# 1_HV_POWER.net
KiCad netlist of a schematic drawn in Altium Designer
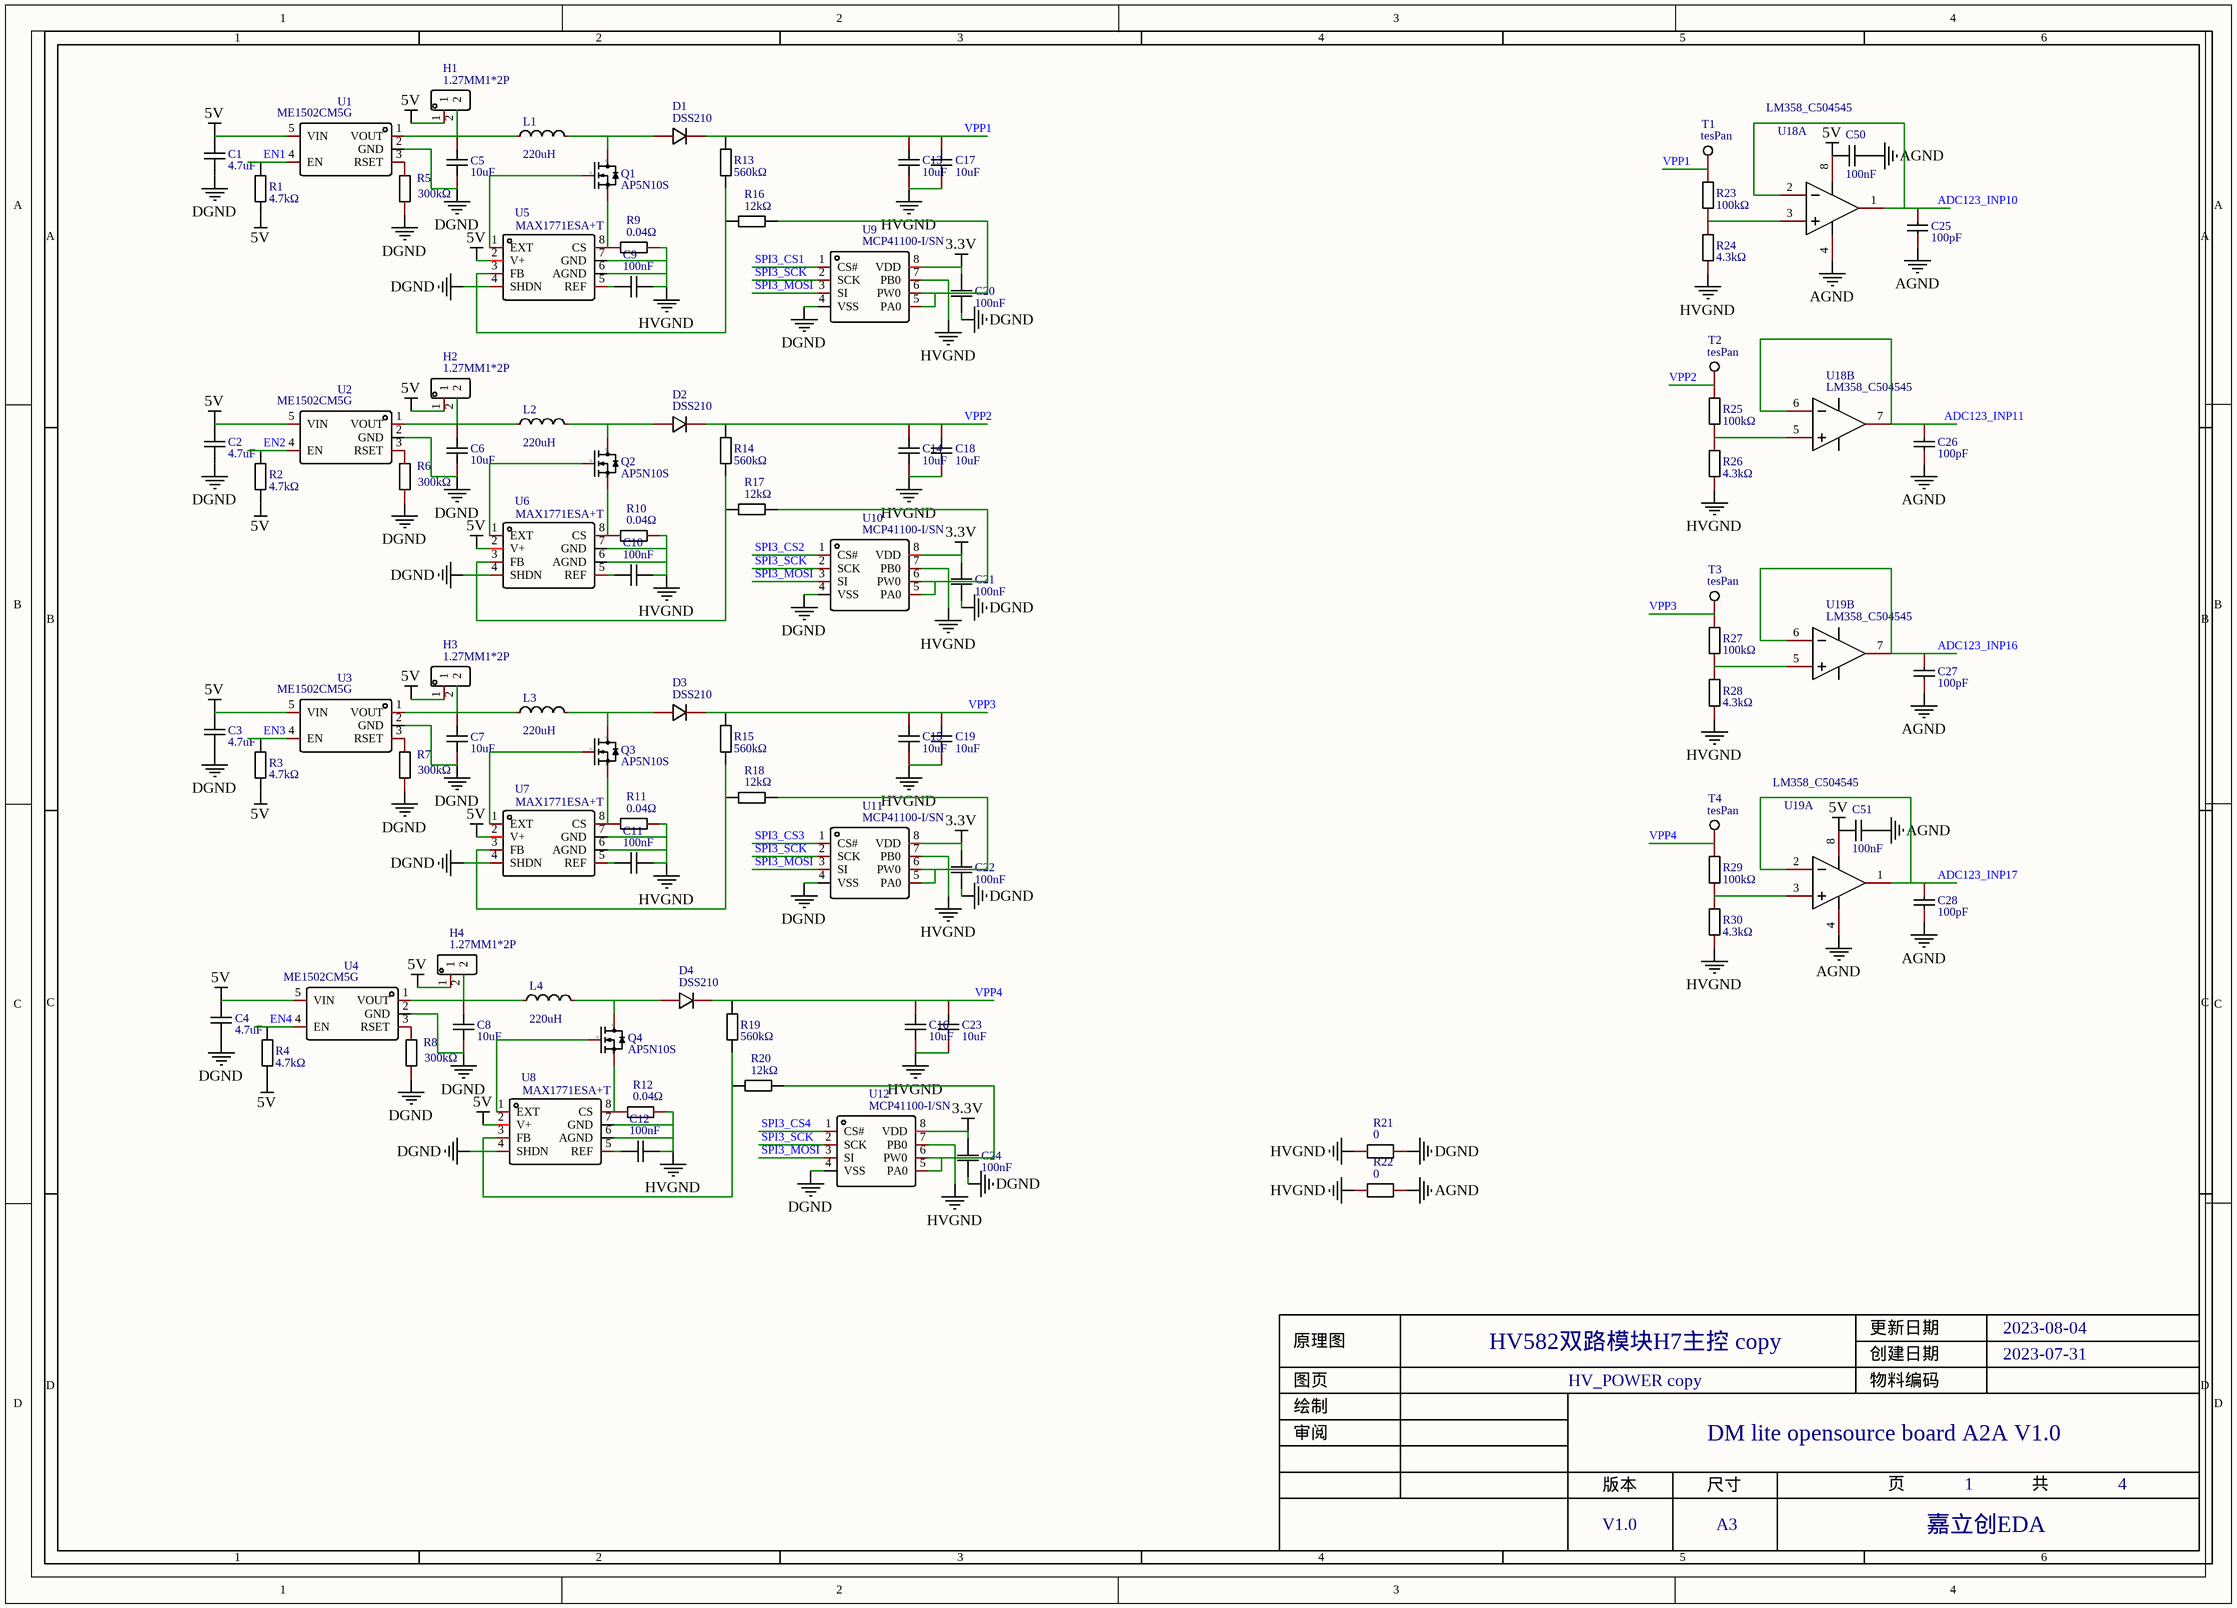
[diagram p0: 1_HV_POWER.schdoc]

(export (version "E")
  (design (tool "Eeschema 10.0.6"))
  (components
    (comp (ref "C1")
      (value "4.7uF")
      (fields
        (field (name "NAME") "4.7uF")
        (field (name "MANUFACTURER PART") "CL05A475MP5NRNC")
        (field (name "MANUFACTURER") "SAMSUNG(三星)")
      )
      (libsource (lib "altium-import") (part "root_1_4.7uF_"))
    )
    (comp (ref "C2")
      (value "4.7uF")
      (fields
        (field (name "NAME") "4.7uF")
        (field (name "MANUFACTURER PART") "CL05A475MP5NRNC")
        (field (name "MANUFACTURER") "SAMSUNG(三星)")
      )
      (libsource (lib "altium-import") (part "root_1_4.7uF_C0402_"))
    )
    (comp (ref "C3")
      (value "4.7uF")
      (fields
        (field (name "NAME") "4.7uF")
        (field (name "MANUFACTURER PART") "CL05A475MP5NRNC")
        (field (name "MANUFACTURER") "SAMSUNG(三星)")
      )
      (libsource (lib "altium-import") (part "root_1_4.7uF_C0402_"))
    )
    (comp (ref "C4")
      (value "4.7uF")
      (fields
        (field (name "NAME") "4.7uF")
        (field (name "MANUFACTURER PART") "CL05A475MP5NRNC")
        (field (name "MANUFACTURER") "SAMSUNG(三星)")
      )
      (libsource (lib "altium-import") (part "root_1_4.7uF_C0402_"))
    )
    (comp (ref "C5")
      (value "10uF")
      (fields
        (field (name "NAME") "10uF")
        (field (name "MANUFACTURER") "Samsung Electro-Mechanics")
        (field (name "MANUFACTURER PART") "CL05A106MP5NUNC")
      )
      (libsource (lib "altium-import") (part "root_1_10uF_C0402_"))
    )
    (comp (ref "C6")
      (value "10uF")
      (fields
        (field (name "NAME") "10uF")
        (field (name "MANUFACTURER") "Samsung Electro-Mechanics")
        (field (name "MANUFACTURER PART") "CL05A106MP5NUNC")
      )
      (libsource (lib "altium-import") (part "root_1_10uF_C0402_"))
    )
    (comp (ref "C7")
      (value "10uF")
      (fields
        (field (name "NAME") "10uF")
        (field (name "MANUFACTURER") "Samsung Electro-Mechanics")
        (field (name "MANUFACTURER PART") "CL05A106MP5NUNC")
      )
      (libsource (lib "altium-import") (part "root_1_10uF_C0402_"))
    )
    (comp (ref "C8")
      (value "10uF")
      (fields
        (field (name "NAME") "10uF")
        (field (name "MANUFACTURER") "Samsung Electro-Mechanics")
        (field (name "MANUFACTURER PART") "CL05A106MP5NUNC")
      )
      (libsource (lib "altium-import") (part "root_1_10uF_C0402_"))
    )
    (comp (ref "C9")
      (value "100nF")
      (fields
        (field (name "NAME") "100nF")
        (field (name "MANUFACTURER PART") "CL05B104KO5NNNC")
        (field (name "MANUFACTURER") "SAMSUNG")
      )
      (libsource (lib "altium-import") (part "root_2_100nF_C0402_NEW_"))
    )
    (comp (ref "C10")
      (value "100nF")
      (fields
        (field (name "NAME") "100nF")
        (field (name "MANUFACTURER PART") "CL05B104KO5NNNC")
        (field (name "MANUFACTURER") "SAMSUNG")
      )
      (libsource (lib "altium-import") (part "root_2_100nF_C0402_NEW_"))
    )
    (comp (ref "C11")
      (value "100nF")
      (fields
        (field (name "NAME") "100nF")
        (field (name "MANUFACTURER PART") "CL05B104KO5NNNC")
        (field (name "MANUFACTURER") "SAMSUNG")
      )
      (libsource (lib "altium-import") (part "root_2_100nF_C0402_NEW_"))
    )
    (comp (ref "C12")
      (value "100nF")
      (fields
        (field (name "NAME") "100nF")
        (field (name "MANUFACTURER PART") "CL05B104KO5NNNC")
        (field (name "MANUFACTURER") "SAMSUNG")
      )
      (libsource (lib "altium-import") (part "root_2_100nF_C0402_NEW_"))
    )
    (comp (ref "C13")
      (value "10uF")
      (fields
        (field (name "NAME") "10uF")
        (field (name "MANUFACTURER") "SANYEAR(叁叶源)")
        (field (name "MANUFACTURER PART") "C1210X7R106K101NT")
      )
      (libsource (lib "altium-import") (part "root_1_10uF_C1210_"))
    )
    (comp (ref "C14")
      (value "10uF")
      (fields
        (field (name "NAME") "10uF")
        (field (name "MANUFACTURER") "SANYEAR(叁叶源)")
        (field (name "MANUFACTURER PART") "C1210X7R106K101NT")
      )
      (libsource (lib "altium-import") (part "root_1_10uF_C1210_"))
    )
    (comp (ref "C15")
      (value "10uF")
      (fields
        (field (name "NAME") "10uF")
        (field (name "MANUFACTURER") "SANYEAR(叁叶源)")
        (field (name "MANUFACTURER PART") "C1210X7R106K101NT")
      )
      (libsource (lib "altium-import") (part "root_1_10uF_C1210_"))
    )
    (comp (ref "C16")
      (value "10uF")
      (fields
        (field (name "NAME") "10uF")
        (field (name "MANUFACTURER") "SANYEAR(叁叶源)")
        (field (name "MANUFACTURER PART") "C1210X7R106K101NT")
      )
      (libsource (lib "altium-import") (part "root_1_10uF_C1210_"))
    )
    (comp (ref "C17")
      (value "10uF")
      (fields
        (field (name "NAME") "10uF")
        (field (name "MANUFACTURER") "SANYEAR(叁叶源)")
        (field (name "MANUFACTURER PART") "C1210X7R106K101NT")
      )
      (libsource (lib "altium-import") (part "root_1_10uF_C1210_"))
    )
    (comp (ref "C18")
      (value "10uF")
      (fields
        (field (name "NAME") "10uF")
        (field (name "MANUFACTURER") "SANYEAR(叁叶源)")
        (field (name "MANUFACTURER PART") "C1210X7R106K101NT")
      )
      (libsource (lib "altium-import") (part "root_1_10uF_C1210_"))
    )
    (comp (ref "C19")
      (value "10uF")
      (fields
        (field (name "NAME") "10uF")
        (field (name "MANUFACTURER") "SANYEAR(叁叶源)")
        (field (name "MANUFACTURER PART") "C1210X7R106K101NT")
      )
      (libsource (lib "altium-import") (part "root_1_10uF_C1210_"))
    )
    (comp (ref "C20")
      (value "100nF")
      (fields
        (field (name "NAME") "100nF")
        (field (name "MANUFACTURER PART") "CL05B104KO5NNNC")
        (field (name "MANUFACTURER") "SAMSUNG")
      )
      (libsource (lib "altium-import") (part "root_3_100nF_C0402_NEW_"))
    )
    (comp (ref "C21")
      (value "100nF")
      (fields
        (field (name "NAME") "100nF")
        (field (name "MANUFACTURER PART") "CL05B104KO5NNNC")
        (field (name "MANUFACTURER") "SAMSUNG")
      )
      (libsource (lib "altium-import") (part "root_3_100nF_C0402_NEW_"))
    )
    (comp (ref "C22")
      (value "100nF")
      (fields
        (field (name "NAME") "100nF")
        (field (name "MANUFACTURER PART") "CL05B104KO5NNNC")
        (field (name "MANUFACTURER") "SAMSUNG")
      )
      (libsource (lib "altium-import") (part "root_3_100nF_C0402_NEW_"))
    )
    (comp (ref "C23")
      (value "10uF")
      (fields
        (field (name "NAME") "10uF")
        (field (name "MANUFACTURER") "SANYEAR(叁叶源)")
        (field (name "MANUFACTURER PART") "C1210X7R106K101NT")
      )
      (libsource (lib "altium-import") (part "root_1_10uF_C1210_"))
    )
    (comp (ref "C24")
      (value "100nF")
      (fields
        (field (name "NAME") "100nF")
        (field (name "MANUFACTURER PART") "CL05B104KO5NNNC")
        (field (name "MANUFACTURER") "SAMSUNG")
      )
      (libsource (lib "altium-import") (part "root_3_100nF_C0402_NEW_"))
    )
    (comp (ref "C25")
      (value "100pF")
      (fields
        (field (name "NAME") "100pF")
        (field (name "MANUFACTURER") "FH")
        (field (name "MANUFACTURER PART") "0402CG101J500NT")
      )
      (libsource (lib "altium-import") (part "root_1_0402CG101J500NT_"))
    )
    (comp (ref "C26")
      (value "100pF")
      (fields
        (field (name "NAME") "100pF")
        (field (name "MANUFACTURER") "FH")
        (field (name "MANUFACTURER PART") "0402CG101J500NT")
      )
      (libsource (lib "altium-import") (part "root_1_0402CG101J500NT_"))
    )
    (comp (ref "C27")
      (value "100pF")
      (fields
        (field (name "NAME") "100pF")
        (field (name "MANUFACTURER") "FH")
        (field (name "MANUFACTURER PART") "0402CG101J500NT")
      )
      (libsource (lib "altium-import") (part "root_1_0402CG101J500NT_"))
    )
    (comp (ref "C28")
      (value "100pF")
      (fields
        (field (name "NAME") "100pF")
        (field (name "MANUFACTURER") "FH")
        (field (name "MANUFACTURER PART") "0402CG101J500NT")
      )
      (libsource (lib "altium-import") (part "root_1_0402CG101J500NT_"))
    )
    (comp (ref "C50")
      (value "100nF")
      (fields
        (field (name "NAME") "100nF")
        (field (name "MANUFACTURER PART") "CL05B104KO5NNNC")
        (field (name "MANUFACTURER") "SAMSUNG")
      )
      (libsource (lib "altium-import") (part "root_0_100nF_C0402_NEW_"))
    )
    (comp (ref "C51")
      (value "100nF")
      (fields
        (field (name "NAME") "100nF")
        (field (name "MANUFACTURER PART") "CL05B104KO5NNNC")
        (field (name "MANUFACTURER") "SAMSUNG")
      )
      (libsource (lib "altium-import") (part "root_0_100nF_C0402_NEW_"))
    )
    (comp (ref "D1")
      (value "DSS210")
      (fields (field (name "NAME") "DSS210") (field (name "MANUFACTURER") "Bourne Semicon (Shenzhen)"))
      (libsource (lib "altium-import") (part "root_0_DSS210_"))
    )
    (comp (ref "D2")
      (value "DSS210")
      (fields (field (name "NAME") "DSS210") (field (name "MANUFACTURER") "Bourne Semicon (Shenzhen)"))
      (libsource (lib "altium-import") (part "root_0_DSS210_SOD-123_L2.8-W1.8-LS3.7-FD_"))
    )
    (comp (ref "D3")
      (value "DSS210")
      (fields (field (name "NAME") "DSS210") (field (name "MANUFACTURER") "Bourne Semicon (Shenzhen)"))
      (libsource (lib "altium-import") (part "root_0_DSS210_SOD-123_L2.8-W1.8-LS3.7-FD_"))
    )
    (comp (ref "D4")
      (value "DSS210")
      (fields (field (name "NAME") "DSS210") (field (name "MANUFACTURER") "Bourne Semicon (Shenzhen)"))
      (libsource (lib "altium-import") (part "root_0_DSS210_SOD-123_L2.8-W1.8-LS3.7-FD_"))
    )
    (comp (ref "H1")
      (value "1.27MM1*2P")
      (fields
        (field (name "NAME") "1.27MM1*2P")
        (field (name "MANUFACTURER") "ReliaPro")
        (field (name "MANUFACTURER PART") "1.27mm1*12P Straight Headers  Pins")
      )
      (libsource (lib "altium-import") (part "root_1_1.27MM1*2P_"))
    )
    (comp (ref "H2")
      (value "1.27MM1*2P")
      (fields
        (field (name "NAME") "1.27MM1*2P")
        (field (name "MANUFACTURER") "ReliaPro")
        (field (name "MANUFACTURER PART") "1.27mm1*12P Straight Headers  Pins")
      )
      (libsource (lib "altium-import") (part "root_1_1.27MM1*2P_1.27MM1*2P_"))
    )
    (comp (ref "H3")
      (value "1.27MM1*2P")
      (fields
        (field (name "NAME") "1.27MM1*2P")
        (field (name "MANUFACTURER") "ReliaPro")
        (field (name "MANUFACTURER PART") "1.27mm1*12P Straight Headers  Pins")
      )
      (libsource (lib "altium-import") (part "root_1_1.27MM1*2P_1.27MM1*2P_"))
    )
    (comp (ref "H4")
      (value "1.27MM1*2P")
      (fields
        (field (name "NAME") "1.27MM1*2P")
        (field (name "MANUFACTURER") "ReliaPro")
        (field (name "MANUFACTURER PART") "1.27mm1*12P Straight Headers  Pins")
      )
      (libsource (lib "altium-import") (part "root_1_1.27MM1*2P_1.27MM1*2P_"))
    )
    (comp (ref "L1")
      (value "220uH")
      (description "电感值:220uH;精度:±20%;额定电流:590mA;")
      (fields (field (name "MANUFACTURER") "YJYCOIN(益嘉源)") (field (name "MANUFACTURER PART") "YNR6045-221M"))
      (libsource (lib "altium-import") (part "root_0_YNR6045-221M_"))
    )
    (comp (ref "L2")
      (value "220uH")
      (description "电感值:220uH;精度:±20%;额定电流:590mA;")
      (fields (field (name "MANUFACTURER") "YJYCOIN(益嘉源)") (field (name "MANUFACTURER PART") "YNR6045-221M"))
      (libsource (lib "altium-import") (part "root_0_YNR6045-221M_"))
    )
    (comp (ref "L3")
      (value "220uH")
      (description "电感值:220uH;精度:±20%;额定电流:590mA;")
      (fields (field (name "MANUFACTURER") "YJYCOIN(益嘉源)") (field (name "MANUFACTURER PART") "YNR6045-221M"))
      (libsource (lib "altium-import") (part "root_0_YNR6045-221M_"))
    )
    (comp (ref "L4")
      (value "220uH")
      (description "电感值:220uH;精度:±20%;额定电流:590mA;")
      (fields (field (name "MANUFACTURER") "YJYCOIN(益嘉源)") (field (name "MANUFACTURER PART") "YNR6045-221M"))
      (libsource (lib "altium-import") (part "root_0_YNR6045-221M_"))
    )
    (comp (ref "Q1")
      (value "AP5N10S")
      (fields (field (name "NAME") "AP5N10S") (field (name "MANUFACTURER") "ALLPOWER(铨力)"))
      (libsource (lib "altium-import") (part "root_0_AP5N10S_"))
    )
    (comp (ref "Q2")
      (value "AP5N10S")
      (fields (field (name "NAME") "AP5N10S") (field (name "MANUFACTURER") "ALLPOWER(铨力)"))
      (libsource (lib "altium-import") (part "root_0_AP5N10S_SOT-23-3_L2.9-W1.6-P1.90-LS2.8-BR_"))
    )
    (comp (ref "Q3")
      (value "AP5N10S")
      (fields (field (name "NAME") "AP5N10S") (field (name "MANUFACTURER") "ALLPOWER(铨力)"))
      (libsource (lib "altium-import") (part "root_0_AP5N10S_SOT-23-3_L2.9-W1.6-P1.90-LS2.8-BR_"))
    )
    (comp (ref "Q4")
      (value "AP5N10S")
      (fields (field (name "NAME") "AP5N10S") (field (name "MANUFACTURER") "ALLPOWER(铨力)"))
      (libsource (lib "altium-import") (part "root_0_AP5N10S_SOT-23-3_L2.9-W1.6-P1.90-LS2.8-BR_"))
    )
    (comp (ref "R1")
      (value "4.7kΩ")
      (fields
        (field (name "NAME") "4.7kΩ")
        (field (name "MANUFACTURER") "UNI-ROYAL(厚声)")
        (field (name "MANUFACTURER PART") "0402WGF4701TCE")
      )
      (libsource (lib "altium-import") (part "root_3_4.7kΩ_"))
    )
    (comp (ref "R2")
      (value "4.7kΩ")
      (fields
        (field (name "NAME") "4.7kΩ")
        (field (name "MANUFACTURER") "UNI-ROYAL(厚声)")
        (field (name "MANUFACTURER PART") "0402WGF4701TCE")
      )
      (libsource (lib "altium-import") (part "root_3_4.7kΩ_R0402_"))
    )
    (comp (ref "R3")
      (value "4.7kΩ")
      (fields
        (field (name "NAME") "4.7kΩ")
        (field (name "MANUFACTURER") "UNI-ROYAL(厚声)")
        (field (name "MANUFACTURER PART") "0402WGF4701TCE")
      )
      (libsource (lib "altium-import") (part "root_3_4.7kΩ_R0402_"))
    )
    (comp (ref "R4")
      (value "4.7kΩ")
      (fields
        (field (name "NAME") "4.7kΩ")
        (field (name "MANUFACTURER") "UNI-ROYAL(厚声)")
        (field (name "MANUFACTURER PART") "0402WGF4701TCE")
      )
      (libsource (lib "altium-import") (part "root_3_4.7kΩ_R0402_"))
    )
    (comp (ref "R5")
      (value "300kΩ")
      (description "电阻类型:厚膜电阻;阻值:300kΩ;精度:±1%;功率:62.5mW;温度系数:±100ppm/℃;最大工作电压:50V;工作温度范围:-55℃~+155℃;")
      (fields
        (field (name "MANUFACTURER") "UNI-ROYAL(厚声)")
        (field (name "MANUFACTURER PART") "0402WGF3003TCE")
      )
      (libsource (lib "altium-import") (part "root_1_0402WGF3003TCE_"))
    )
    (comp (ref "R6")
      (value "300kΩ")
      (description "电阻类型:厚膜电阻;阻值:300kΩ;精度:±1%;功率:62.5mW;温度系数:±100ppm/℃;最大工作电压:50V;工作温度范围:-55℃~+155℃;")
      (fields
        (field (name "MANUFACTURER") "UNI-ROYAL(厚声)")
        (field (name "MANUFACTURER PART") "0402WGF3003TCE")
      )
      (libsource (lib "altium-import") (part "root_1_0402WGF3003TCE_"))
    )
    (comp (ref "R7")
      (value "300kΩ")
      (description "电阻类型:厚膜电阻;阻值:300kΩ;精度:±1%;功率:62.5mW;温度系数:±100ppm/℃;最大工作电压:50V;工作温度范围:-55℃~+155℃;")
      (fields
        (field (name "MANUFACTURER") "UNI-ROYAL(厚声)")
        (field (name "MANUFACTURER PART") "0402WGF3003TCE")
      )
      (libsource (lib "altium-import") (part "root_1_0402WGF3003TCE_"))
    )
    (comp (ref "R8")
      (value "300kΩ")
      (description "电阻类型:厚膜电阻;阻值:300kΩ;精度:±1%;功率:62.5mW;温度系数:±100ppm/℃;最大工作电压:50V;工作温度范围:-55℃~+155℃;")
      (fields
        (field (name "MANUFACTURER") "UNI-ROYAL(厚声)")
        (field (name "MANUFACTURER PART") "0402WGF3003TCE")
      )
      (libsource (lib "altium-import") (part "root_1_0402WGF3003TCE_"))
    )
    (comp (ref "R9")
      (value "0.04Ω")
      (fields
        (field (name "NAME") "0.04Ω")
        (field (name "MANUFACTURER") "Walter Elec")
        (field (name "MANUFACTURER PART") "STE0805MW75R040F")
      )
      (libsource (lib "altium-import") (part "root_0_0.04Ω_"))
    )
    (comp (ref "R10")
      (value "0.04Ω")
      (fields
        (field (name "NAME") "0.04Ω")
        (field (name "MANUFACTURER") "Walter Elec")
        (field (name "MANUFACTURER PART") "STE0805MW75R040F")
      )
      (libsource (lib "altium-import") (part "root_0_0.04Ω_R0805_"))
    )
    (comp (ref "R11")
      (value "0.04Ω")
      (fields
        (field (name "NAME") "0.04Ω")
        (field (name "MANUFACTURER") "Walter Elec")
        (field (name "MANUFACTURER PART") "STE0805MW75R040F")
      )
      (libsource (lib "altium-import") (part "root_0_0.04Ω_R0805_"))
    )
    (comp (ref "R12")
      (value "0.04Ω")
      (fields
        (field (name "NAME") "0.04Ω")
        (field (name "MANUFACTURER") "Walter Elec")
        (field (name "MANUFACTURER PART") "STE0805MW75R040F")
      )
      (libsource (lib "altium-import") (part "root_0_0.04Ω_R0805_"))
    )
    (comp (ref "R13")
      (value "560kΩ")
      (fields
        (field (name "NAME") "560kΩ")
        (field (name "MANUFACTURER") "UNI-ROYAL(厚声)")
        (field (name "MANUFACTURER PART") "0402WGF5603TCE")
      )
      (libsource (lib "altium-import") (part "root_1_560kΩ_"))
    )
    (comp (ref "R14")
      (value "560kΩ")
      (fields
        (field (name "NAME") "560kΩ")
        (field (name "MANUFACTURER") "UNI-ROYAL(厚声)")
        (field (name "MANUFACTURER PART") "0402WGF5603TCE")
      )
      (libsource (lib "altium-import") (part "root_1_560kΩ_R0402_"))
    )
    (comp (ref "R15")
      (value "560kΩ")
      (fields
        (field (name "NAME") "560kΩ")
        (field (name "MANUFACTURER") "UNI-ROYAL(厚声)")
        (field (name "MANUFACTURER PART") "0402WGF5603TCE")
      )
      (libsource (lib "altium-import") (part "root_1_560kΩ_R0402_"))
    )
    (comp (ref "R16")
      (value "12kΩ")
      (fields
        (field (name "NAME") "12kΩ")
        (field (name "MANUFACTURER") "UniOhm")
        (field (name "MANUFACTURER PART") "0402WGF1202TCE")
      )
      (libsource (lib "altium-import") (part "root_0_12kΩ_"))
    )
    (comp (ref "R17")
      (value "12kΩ")
      (fields
        (field (name "NAME") "12kΩ")
        (field (name "MANUFACTURER") "UniOhm")
        (field (name "MANUFACTURER PART") "0402WGF1202TCE")
      )
      (libsource (lib "altium-import") (part "root_0_12kΩ_R0402_"))
    )
    (comp (ref "R18")
      (value "12kΩ")
      (fields
        (field (name "NAME") "12kΩ")
        (field (name "MANUFACTURER") "UniOhm")
        (field (name "MANUFACTURER PART") "0402WGF1202TCE")
      )
      (libsource (lib "altium-import") (part "root_0_12kΩ_R0402_"))
    )
    (comp (ref "R19")
      (value "560kΩ")
      (fields
        (field (name "NAME") "560kΩ")
        (field (name "MANUFACTURER") "UNI-ROYAL(厚声)")
        (field (name "MANUFACTURER PART") "0402WGF5603TCE")
      )
      (libsource (lib "altium-import") (part "root_1_560kΩ_R0402_"))
    )
    (comp (ref "R20")
      (value "12kΩ")
      (fields
        (field (name "NAME") "12kΩ")
        (field (name "MANUFACTURER") "UniOhm")
        (field (name "MANUFACTURER PART") "0402WGF1202TCE")
      )
      (libsource (lib "altium-import") (part "root_0_12kΩ_R0402_"))
    )
    (comp (ref "R21")
      (value "0")
      (fields (field (name "NAME") "0"))
      (libsource (lib "altium-import") (part "root_0_0_"))
    )
    (comp (ref "R22")
      (value "0")
      (fields (field (name "NAME") "0"))
      (libsource (lib "altium-import") (part "root_0_0_"))
    )
    (comp (ref "R23")
      (value "100kΩ")
      (fields
        (field (name "NAME") "100kΩ")
        (field (name "MANUFACTURER") "UniOhm")
        (field (name "MANUFACTURER PART") "0402WGF1003TCE")
      )
      (libsource (lib "altium-import") (part "root_1_0402WGF1003TCE_"))
    )
    (comp (ref "R24")
      (value "4.3kΩ")
      (fields
        (field (name "NAME") "4.3kΩ")
        (field (name "MANUFACTURER") "UniOhm")
        (field (name "MANUFACTURER PART") "0402WGJ0432TCE")
      )
      (libsource (lib "altium-import") (part "root_1_0402WGJ0432TCE_"))
    )
    (comp (ref "R25")
      (value "100kΩ")
      (fields
        (field (name "NAME") "100kΩ")
        (field (name "MANUFACTURER") "UniOhm")
        (field (name "MANUFACTURER PART") "0402WGF1003TCE")
      )
      (libsource (lib "altium-import") (part "root_1_0402WGF1003TCE_"))
    )
    (comp (ref "R26")
      (value "4.3kΩ")
      (fields
        (field (name "NAME") "4.3kΩ")
        (field (name "MANUFACTURER") "UniOhm")
        (field (name "MANUFACTURER PART") "0402WGJ0432TCE")
      )
      (libsource (lib "altium-import") (part "root_1_0402WGJ0432TCE_"))
    )
    (comp (ref "R27")
      (value "100kΩ")
      (fields
        (field (name "NAME") "100kΩ")
        (field (name "MANUFACTURER") "UniOhm")
        (field (name "MANUFACTURER PART") "0402WGF1003TCE")
      )
      (libsource (lib "altium-import") (part "root_1_0402WGF1003TCE_"))
    )
    (comp (ref "R28")
      (value "4.3kΩ")
      (fields
        (field (name "NAME") "4.3kΩ")
        (field (name "MANUFACTURER") "UniOhm")
        (field (name "MANUFACTURER PART") "0402WGJ0432TCE")
      )
      (libsource (lib "altium-import") (part "root_1_0402WGJ0432TCE_"))
    )
    (comp (ref "R29")
      (value "100kΩ")
      (fields
        (field (name "NAME") "100kΩ")
        (field (name "MANUFACTURER") "UniOhm")
        (field (name "MANUFACTURER PART") "0402WGF1003TCE")
      )
      (libsource (lib "altium-import") (part "root_1_0402WGF1003TCE_"))
    )
    (comp (ref "R30")
      (value "4.3kΩ")
      (fields
        (field (name "NAME") "4.3kΩ")
        (field (name "MANUFACTURER") "UniOhm")
        (field (name "MANUFACTURER PART") "0402WGJ0432TCE")
      )
      (libsource (lib "altium-import") (part "root_1_0402WGJ0432TCE_"))
    )
    (comp (ref "T1")
      (value "tesPan")
      (fields (field (name "NAME") "tesPan"))
      (libsource (lib "altium-import") (part "root_0_tesPan_"))
    )
    (comp (ref "T2")
      (value "tesPan")
      (fields (field (name "NAME") "tesPan"))
      (libsource (lib "altium-import") (part "root_0_tesPan_"))
    )
    (comp (ref "T3")
      (value "tesPan")
      (fields (field (name "NAME") "tesPan"))
      (libsource (lib "altium-import") (part "root_0_tesPan_"))
    )
    (comp (ref "T4")
      (value "tesPan")
      (fields (field (name "NAME") "tesPan"))
      (libsource (lib "altium-import") (part "root_0_tesPan_"))
    )
    (comp (ref "U1")
      (value "ME1502CM5G")
      (fields (field (name "NAME") "ME1502CM5G") (field (name "MANUFACTURER") "MICRONE(南京微盟)"))
      (libsource (lib "altium-import") (part "root_0_ME1502CM5G_"))
    )
    (comp (ref "U2")
      (value "ME1502CM5G")
      (fields (field (name "NAME") "ME1502CM5G") (field (name "MANUFACTURER") "MICRONE(南京微盟)"))
      (libsource (lib "altium-import") (part "root_0_ME1502CM5G_SOT-23-5_L3.0-W1.5-P0.95-LS2.8-BL_"))
    )
    (comp (ref "U3")
      (value "ME1502CM5G")
      (fields (field (name "NAME") "ME1502CM5G") (field (name "MANUFACTURER") "MICRONE(南京微盟)"))
      (libsource (lib "altium-import") (part "root_0_ME1502CM5G_SOT-23-5_L3.0-W1.5-P0.95-LS2.8-BL_"))
    )
    (comp (ref "U4")
      (value "ME1502CM5G")
      (fields (field (name "NAME") "ME1502CM5G") (field (name "MANUFACTURER") "MICRONE(南京微盟)"))
      (libsource (lib "altium-import") (part "root_0_ME1502CM5G_SOT-23-5_L3.0-W1.5-P0.95-LS2.8-BL_"))
    )
    (comp (ref "U5")
      (value "MAX1771ESA+T")
      (fields (field (name "NAME") "MAX1771ESA+T") (field (name "MANUFACTURER") "Maxim Integrated"))
      (libsource (lib "altium-import") (part "root_0_MAX1771ESA+T_"))
    )
    (comp (ref "U6")
      (value "MAX1771ESA+T")
      (fields (field (name "NAME") "MAX1771ESA+T") (field (name "MANUFACTURER") "Maxim Integrated"))
      (libsource (lib "altium-import") (part "root_0_MAX1771ESA+T_SO-8_L4.9-W3.9-P1.27-LS5.9-BL_"))
    )
    (comp (ref "U7")
      (value "MAX1771ESA+T")
      (fields (field (name "NAME") "MAX1771ESA+T") (field (name "MANUFACTURER") "Maxim Integrated"))
      (libsource (lib "altium-import") (part "root_0_MAX1771ESA+T_SO-8_L4.9-W3.9-P1.27-LS5.9-BL_"))
    )
    (comp (ref "U8")
      (value "MAX1771ESA+T")
      (fields (field (name "NAME") "MAX1771ESA+T") (field (name "MANUFACTURER") "Maxim Integrated"))
      (libsource (lib "altium-import") (part "root_0_MAX1771ESA+T_SO-8_L4.9-W3.9-P1.27-LS5.9-BL_"))
    )
    (comp (ref "U9")
      (value "MCP41100-I/SN")
      (fields (field (name "NAME") "MCP41100-I/SN") (field (name "MANUFACTURER") "MICROCHIP"))
      (libsource (lib "altium-import") (part "root_0_MCP41100-I/SN_"))
    )
    (comp (ref "U10")
      (value "MCP41100-I/SN")
      (fields (field (name "NAME") "MCP41100-I/SN") (field (name "MANUFACTURER") "MICROCHIP"))
      (libsource (lib "altium-import") (part "root_0_MCP41100-I/SN_SOIC-8_L4.9-W3.9-P1.27-LS6.0-BL_"))
    )
    (comp (ref "U11")
      (value "MCP41100-I/SN")
      (fields (field (name "NAME") "MCP41100-I/SN") (field (name "MANUFACTURER") "MICROCHIP"))
      (libsource (lib "altium-import") (part "root_0_MCP41100-I/SN_SOIC-8_L4.9-W3.9-P1.27-LS6.0-BL_"))
    )
    (comp (ref "U12")
      (value "MCP41100-I/SN")
      (fields (field (name "NAME") "MCP41100-I/SN") (field (name "MANUFACTURER") "MICROCHIP"))
      (libsource (lib "altium-import") (part "root_0_MCP41100-I/SN_SOIC-8_L4.9-W3.9-P1.27-LS6.0-BL_"))
    )
    (comp (ref "U18")
      (value "LM358_C504545")
      (fields
        (field (name "NAME") "LM358_C504545")
        (field (name "MANUFACTURER") "Gcore")
        (field (name "MANUFACTURER PART") "LM358")
      )
      (libsource (lib "altium-import") (part "root_0_LM358_"))
    )
    (comp (ref "U19")
      (value "LM358_C504545")
      (fields
        (field (name "NAME") "LM358_C504545")
        (field (name "MANUFACTURER") "Gcore")
        (field (name "MANUFACTURER PART") "LM358")
      )
      (libsource (lib "altium-import") (part "root_0_LM358_"))
    )
  )
  (nets
    (net (code "1") (name "/ADC123_INP10") (class "Default")
      (node (ref "C25") (pin "2") (pinfunction "2_2") (pintype "passive"))
      (node (ref "U18") (pin "1") (pinfunction "OUT1_1") (pintype "passive"))
      (node (ref "U18") (pin "2") (pinfunction "IN1-_2") (pintype "passive"))
    )
    (net (code "2") (name "/ADC123_INP11") (class "Default")
      (node (ref "C26") (pin "2") (pinfunction "2_2") (pintype "passive"))
      (node (ref "U18") (pin "6") (pinfunction "IN2-_6") (pintype "passive"))
      (node (ref "U18") (pin "7") (pinfunction "OUT2_7") (pintype "passive"))
    )
    (net (code "3") (name "/ADC123_INP16") (class "Default")
      (node (ref "C27") (pin "2") (pinfunction "2_2") (pintype "passive"))
      (node (ref "U19") (pin "6") (pinfunction "IN2-_6") (pintype "passive"))
      (node (ref "U19") (pin "7") (pinfunction "OUT2_7") (pintype "passive"))
    )
    (net (code "4") (name "/ADC123_INP17") (class "Default")
      (node (ref "C28") (pin "2") (pinfunction "2_2") (pintype "passive"))
      (node (ref "U19") (pin "1") (pinfunction "OUT1_1") (pintype "passive"))
      (node (ref "U19") (pin "2") (pinfunction "IN1-_2") (pintype "passive"))
    )
    (net (code "5") (name "/EN1") (class "Default")
      (node (ref "R1") (pin "1") (pinfunction "1_1") (pintype "passive"))
      (node (ref "U1") (pin "4") (pinfunction "EN_4") (pintype "passive"))
    )
    (net (code "6") (name "/EN2") (class "Default")
      (node (ref "R2") (pin "1") (pinfunction "1_1") (pintype "passive"))
      (node (ref "U2") (pin "4") (pinfunction "EN_4") (pintype "passive"))
    )
    (net (code "7") (name "/EN3") (class "Default")
      (node (ref "R3") (pin "1") (pinfunction "1_1") (pintype "passive"))
      (node (ref "U3") (pin "4") (pinfunction "EN_4") (pintype "passive"))
    )
    (net (code "8") (name "/EN4") (class "Default")
      (node (ref "R4") (pin "1") (pinfunction "1_1") (pintype "passive"))
      (node (ref "U4") (pin "4") (pinfunction "EN_4") (pintype "passive"))
    )
    (net (code "9") (name "/SPI3_CS1") (class "Default")
      (node (ref "U9") (pin "1") (pinfunction "CS#_1") (pintype "passive"))
    )
    (net (code "10") (name "/SPI3_CS2") (class "Default")
      (node (ref "U10") (pin "1") (pinfunction "CS#_1") (pintype "passive"))
    )
    (net (code "11") (name "/SPI3_CS3") (class "Default")
      (node (ref "U11") (pin "1") (pinfunction "CS#_1") (pintype "passive"))
    )
    (net (code "12") (name "/SPI3_CS4") (class "Default")
      (node (ref "U12") (pin "1") (pinfunction "CS#_1") (pintype "passive"))
    )
    (net (code "13") (name "/SPI3_MOSI") (class "Default")
      (node (ref "U10") (pin "3") (pinfunction "SI_3") (pintype "passive"))
      (node (ref "U11") (pin "3") (pinfunction "SI_3") (pintype "passive"))
      (node (ref "U12") (pin "3") (pinfunction "SI_3") (pintype "passive"))
      (node (ref "U9") (pin "3") (pinfunction "SI_3") (pintype "passive"))
    )
    (net (code "14") (name "/SPI3_SCK") (class "Default")
      (node (ref "U10") (pin "2") (pinfunction "SCK_2") (pintype "passive"))
      (node (ref "U11") (pin "2") (pinfunction "SCK_2") (pintype "passive"))
      (node (ref "U12") (pin "2") (pinfunction "SCK_2") (pintype "passive"))
      (node (ref "U9") (pin "2") (pinfunction "SCK_2") (pintype "passive"))
    )
    (net (code "15") (name "/VPP1") (class "Default")
      (node (ref "C13") (pin "2") (pinfunction "2_2") (pintype "passive"))
      (node (ref "C17") (pin "2") (pinfunction "2_2") (pintype "passive"))
      (node (ref "D1") (pin "2") (pinfunction "K_2") (pintype "passive"))
      (node (ref "R13") (pin "2") (pinfunction "2_2") (pintype "passive"))
      (node (ref "R23") (pin "2") (pinfunction "2_2") (pintype "passive"))
      (node (ref "T1") (pin "1") (pinfunction "1_1") (pintype "passive"))
    )
    (net (code "16") (name "/VPP2") (class "Default")
      (node (ref "C14") (pin "2") (pinfunction "2_2") (pintype "passive"))
      (node (ref "C18") (pin "2") (pinfunction "2_2") (pintype "passive"))
      (node (ref "D2") (pin "2") (pinfunction "K_2") (pintype "passive"))
      (node (ref "R14") (pin "2") (pinfunction "2_2") (pintype "passive"))
      (node (ref "R25") (pin "2") (pinfunction "2_2") (pintype "passive"))
      (node (ref "T2") (pin "1") (pinfunction "1_1") (pintype "passive"))
    )
    (net (code "17") (name "/VPP3") (class "Default")
      (node (ref "C15") (pin "2") (pinfunction "2_2") (pintype "passive"))
      (node (ref "C19") (pin "2") (pinfunction "2_2") (pintype "passive"))
      (node (ref "D3") (pin "2") (pinfunction "K_2") (pintype "passive"))
      (node (ref "R15") (pin "2") (pinfunction "2_2") (pintype "passive"))
      (node (ref "R27") (pin "2") (pinfunction "2_2") (pintype "passive"))
      (node (ref "T3") (pin "1") (pinfunction "1_1") (pintype "passive"))
    )
    (net (code "18") (name "/VPP4") (class "Default")
      (node (ref "C16") (pin "2") (pinfunction "2_2") (pintype "passive"))
      (node (ref "C23") (pin "2") (pinfunction "2_2") (pintype "passive"))
      (node (ref "D4") (pin "2") (pinfunction "K_2") (pintype "passive"))
      (node (ref "R19") (pin "2") (pinfunction "2_2") (pintype "passive"))
      (node (ref "R29") (pin "2") (pinfunction "2_2") (pintype "passive"))
      (node (ref "T4") (pin "1") (pinfunction "1_1") (pintype "passive"))
    )
    (net (code "19") (name "3.3V") (class "Default")
      (node (ref "C20") (pin "1") (pinfunction "1_1") (pintype "passive"))
      (node (ref "C21") (pin "1") (pinfunction "1_1") (pintype "passive"))
      (node (ref "C22") (pin "1") (pinfunction "1_1") (pintype "passive"))
      (node (ref "C24") (pin "1") (pinfunction "1_1") (pintype "passive"))
      (node (ref "U10") (pin "8") (pinfunction "VDD_8") (pintype "passive"))
      (node (ref "U11") (pin "8") (pinfunction "VDD_8") (pintype "passive"))
      (node (ref "U12") (pin "8") (pinfunction "VDD_8") (pintype "passive"))
      (node (ref "U9") (pin "8") (pinfunction "VDD_8") (pintype "passive"))
    )
    (net (code "20") (name "5V") (class "Default")
      (node (ref "C1") (pin "2") (pinfunction "2_2") (pintype "passive"))
      (node (ref "C2") (pin "2") (pinfunction "2_2") (pintype "passive"))
      (node (ref "C3") (pin "2") (pinfunction "2_2") (pintype "passive"))
      (node (ref "C4") (pin "2") (pinfunction "2_2") (pintype "passive"))
      (node (ref "C50") (pin "1") (pinfunction "1_1") (pintype "passive"))
      (node (ref "C51") (pin "1") (pinfunction "1_1") (pintype "passive"))
      (node (ref "H1") (pin "1") (pinfunction "1_1") (pintype "passive"))
      (node (ref "H2") (pin "1") (pinfunction "1_1") (pintype "passive"))
      (node (ref "H3") (pin "1") (pinfunction "1_1") (pintype "passive"))
      (node (ref "H4") (pin "1") (pinfunction "1_1") (pintype "passive"))
      (node (ref "R1") (pin "2") (pinfunction "2_2") (pintype "passive"))
      (node (ref "R2") (pin "2") (pinfunction "2_2") (pintype "passive"))
      (node (ref "R3") (pin "2") (pinfunction "2_2") (pintype "passive"))
      (node (ref "R4") (pin "2") (pinfunction "2_2") (pintype "passive"))
      (node (ref "U1") (pin "5") (pinfunction "VIN_5") (pintype "passive"))
      (node (ref "U18") (pin "8") (pinfunction "VCC_8") (pintype "passive"))
      (node (ref "U19") (pin "8") (pinfunction "VCC_8") (pintype "passive"))
      (node (ref "U2") (pin "5") (pinfunction "VIN_5") (pintype "passive"))
      (node (ref "U3") (pin "5") (pinfunction "VIN_5") (pintype "passive"))
      (node (ref "U4") (pin "5") (pinfunction "VIN_5") (pintype "passive"))
      (node (ref "U5") (pin "2") (pinfunction "V+_2") (pintype "passive"))
      (node (ref "U6") (pin "2") (pinfunction "V+_2") (pintype "passive"))
      (node (ref "U7") (pin "2") (pinfunction "V+_2") (pintype "passive"))
      (node (ref "U8") (pin "2") (pinfunction "V+_2") (pintype "passive"))
    )
    (net (code "21") (name "AGND") (class "Default")
      (node (ref "C25") (pin "1") (pinfunction "1_1") (pintype "passive"))
      (node (ref "C26") (pin "1") (pinfunction "1_1") (pintype "passive"))
      (node (ref "C27") (pin "1") (pinfunction "1_1") (pintype "passive"))
      (node (ref "C28") (pin "1") (pinfunction "1_1") (pintype "passive"))
      (node (ref "C50") (pin "2") (pinfunction "2_2") (pintype "passive"))
      (node (ref "C51") (pin "2") (pinfunction "2_2") (pintype "passive"))
      (node (ref "R22") (pin "2") (pinfunction "2_2") (pintype "passive"))
      (node (ref "U18") (pin "4") (pinfunction "GND_4") (pintype "passive"))
      (node (ref "U19") (pin "4") (pinfunction "GND_4") (pintype "passive"))
    )
    (net (code "22") (name "DGND") (class "Default")
      (node (ref "C1") (pin "1") (pinfunction "1_1") (pintype "passive"))
      (node (ref "C2") (pin "1") (pinfunction "1_1") (pintype "passive"))
      (node (ref "C20") (pin "2") (pinfunction "2_2") (pintype "passive"))
      (node (ref "C21") (pin "2") (pinfunction "2_2") (pintype "passive"))
      (node (ref "C22") (pin "2") (pinfunction "2_2") (pintype "passive"))
      (node (ref "C24") (pin "2") (pinfunction "2_2") (pintype "passive"))
      (node (ref "C3") (pin "1") (pinfunction "1_1") (pintype "passive"))
      (node (ref "C4") (pin "1") (pinfunction "1_1") (pintype "passive"))
      (node (ref "C5") (pin "1") (pinfunction "1_1") (pintype "passive"))
      (node (ref "C6") (pin "1") (pinfunction "1_1") (pintype "passive"))
      (node (ref "C7") (pin "1") (pinfunction "1_1") (pintype "passive"))
      (node (ref "C8") (pin "1") (pinfunction "1_1") (pintype "passive"))
      (node (ref "R21") (pin "2") (pinfunction "2_2") (pintype "passive"))
      (node (ref "R5") (pin "1") (pinfunction "1_1") (pintype "passive"))
      (node (ref "R6") (pin "1") (pinfunction "1_1") (pintype "passive"))
      (node (ref "R7") (pin "1") (pinfunction "1_1") (pintype "passive"))
      (node (ref "R8") (pin "1") (pinfunction "1_1") (pintype "passive"))
      (node (ref "U1") (pin "2") (pinfunction "GND_2") (pintype "passive"))
      (node (ref "U10") (pin "4") (pinfunction "VSS_4") (pintype "passive"))
      (node (ref "U11") (pin "4") (pinfunction "VSS_4") (pintype "passive"))
      (node (ref "U12") (pin "4") (pinfunction "VSS_4") (pintype "passive"))
      (node (ref "U2") (pin "2") (pinfunction "GND_2") (pintype "passive"))
      (node (ref "U3") (pin "2") (pinfunction "GND_2") (pintype "passive"))
      (node (ref "U4") (pin "2") (pinfunction "GND_2") (pintype "passive"))
      (node (ref "U5") (pin "4") (pinfunction "SHDN_4") (pintype "passive"))
      (node (ref "U6") (pin "4") (pinfunction "SHDN_4") (pintype "passive"))
      (node (ref "U7") (pin "4") (pinfunction "SHDN_4") (pintype "passive"))
      (node (ref "U8") (pin "4") (pinfunction "SHDN_4") (pintype "passive"))
      (node (ref "U9") (pin "4") (pinfunction "VSS_4") (pintype "passive"))
    )
    (net (code "23") (name "HVGND") (class "Default")
      (node (ref "C10") (pin "1") (pinfunction "1_1") (pintype "passive"))
      (node (ref "C11") (pin "1") (pinfunction "1_1") (pintype "passive"))
      (node (ref "C12") (pin "1") (pinfunction "1_1") (pintype "passive"))
      (node (ref "C13") (pin "1") (pinfunction "1_1") (pintype "passive"))
      (node (ref "C14") (pin "1") (pinfunction "1_1") (pintype "passive"))
      (node (ref "C15") (pin "1") (pinfunction "1_1") (pintype "passive"))
      (node (ref "C16") (pin "1") (pinfunction "1_1") (pintype "passive"))
      (node (ref "C17") (pin "1") (pinfunction "1_1") (pintype "passive"))
      (node (ref "C18") (pin "1") (pinfunction "1_1") (pintype "passive"))
      (node (ref "C19") (pin "1") (pinfunction "1_1") (pintype "passive"))
      (node (ref "C23") (pin "1") (pinfunction "1_1") (pintype "passive"))
      (node (ref "C9") (pin "1") (pinfunction "1_1") (pintype "passive"))
      (node (ref "R10") (pin "2") (pinfunction "2_2") (pintype "passive"))
      (node (ref "R11") (pin "2") (pinfunction "2_2") (pintype "passive"))
      (node (ref "R12") (pin "2") (pinfunction "2_2") (pintype "passive"))
      (node (ref "R21") (pin "1") (pinfunction "1_1") (pintype "passive"))
      (node (ref "R22") (pin "1") (pinfunction "1_1") (pintype "passive"))
      (node (ref "R24") (pin "1") (pinfunction "1_1") (pintype "passive"))
      (node (ref "R26") (pin "1") (pinfunction "1_1") (pintype "passive"))
      (node (ref "R28") (pin "1") (pinfunction "1_1") (pintype "passive"))
      (node (ref "R30") (pin "1") (pinfunction "1_1") (pintype "passive"))
      (node (ref "R9") (pin "2") (pinfunction "2_2") (pintype "passive"))
      (node (ref "U10") (pin "7") (pinfunction "PB0_7") (pintype "passive"))
      (node (ref "U11") (pin "7") (pinfunction "PB0_7") (pintype "passive"))
      (node (ref "U12") (pin "7") (pinfunction "PB0_7") (pintype "passive"))
      (node (ref "U5") (pin "6") (pinfunction "AGND_6") (pintype "passive"))
      (node (ref "U5") (pin "7") (pinfunction "GND_7") (pintype "passive"))
      (node (ref "U6") (pin "6") (pinfunction "AGND_6") (pintype "passive"))
      (node (ref "U6") (pin "7") (pinfunction "GND_7") (pintype "passive"))
      (node (ref "U7") (pin "6") (pinfunction "AGND_6") (pintype "passive"))
      (node (ref "U7") (pin "7") (pinfunction "GND_7") (pintype "passive"))
      (node (ref "U8") (pin "6") (pinfunction "AGND_6") (pintype "passive"))
      (node (ref "U8") (pin "7") (pinfunction "GND_7") (pintype "passive"))
      (node (ref "U9") (pin "7") (pinfunction "PB0_7") (pintype "passive"))
    )
    (net (code "24") (name "Net-(D1-A)") (class "Default")
      (node (ref "D1") (pin "1") (pinfunction "A_1") (pintype "passive"))
      (node (ref "L1") (pin "2") (pinfunction "2_2") (pintype "passive"))
      (node (ref "Q1") (pin "3") (pinfunction "D_3") (pintype "passive"))
    )
    (net (code "25") (name "Net-(D2-A)") (class "Default")
      (node (ref "D2") (pin "1") (pinfunction "A_1") (pintype "passive"))
      (node (ref "L2") (pin "2") (pinfunction "2_2") (pintype "passive"))
      (node (ref "Q2") (pin "3") (pinfunction "D_3") (pintype "passive"))
    )
    (net (code "26") (name "Net-(D3-A)") (class "Default")
      (node (ref "D3") (pin "1") (pinfunction "A_1") (pintype "passive"))
      (node (ref "L3") (pin "2") (pinfunction "2_2") (pintype "passive"))
      (node (ref "Q3") (pin "3") (pinfunction "D_3") (pintype "passive"))
    )
    (net (code "27") (name "Net-(D4-A)") (class "Default")
      (node (ref "D4") (pin "1") (pinfunction "A_1") (pintype "passive"))
      (node (ref "L4") (pin "2") (pinfunction "2_2") (pintype "passive"))
      (node (ref "Q4") (pin "3") (pinfunction "D_3") (pintype "passive"))
    )
    (net (code "28") (name "Net-(Q1-G)") (class "Default")
      (node (ref "Q1") (pin "1") (pinfunction "G_1") (pintype "passive"))
      (node (ref "U5") (pin "1") (pinfunction "EXT_1") (pintype "passive"))
    )
    (net (code "29") (name "Net-(Q1-S)") (class "Default")
      (node (ref "Q1") (pin "2") (pinfunction "S_2") (pintype "passive"))
      (node (ref "R9") (pin "1") (pinfunction "1_1") (pintype "passive"))
      (node (ref "U5") (pin "8") (pinfunction "CS_8") (pintype "passive"))
    )
    (net (code "30") (name "Net-(Q2-G)") (class "Default")
      (node (ref "Q2") (pin "1") (pinfunction "G_1") (pintype "passive"))
      (node (ref "U6") (pin "1") (pinfunction "EXT_1") (pintype "passive"))
    )
    (net (code "31") (name "Net-(Q2-S)") (class "Default")
      (node (ref "Q2") (pin "2") (pinfunction "S_2") (pintype "passive"))
      (node (ref "R10") (pin "1") (pinfunction "1_1") (pintype "passive"))
      (node (ref "U6") (pin "8") (pinfunction "CS_8") (pintype "passive"))
    )
    (net (code "32") (name "Net-(Q3-G)") (class "Default")
      (node (ref "Q3") (pin "1") (pinfunction "G_1") (pintype "passive"))
      (node (ref "U7") (pin "1") (pinfunction "EXT_1") (pintype "passive"))
    )
    (net (code "33") (name "Net-(Q3-S)") (class "Default")
      (node (ref "Q3") (pin "2") (pinfunction "S_2") (pintype "passive"))
      (node (ref "R11") (pin "1") (pinfunction "1_1") (pintype "passive"))
      (node (ref "U7") (pin "8") (pinfunction "CS_8") (pintype "passive"))
    )
    (net (code "34") (name "Net-(Q4-G)") (class "Default")
      (node (ref "Q4") (pin "1") (pinfunction "G_1") (pintype "passive"))
      (node (ref "U8") (pin "1") (pinfunction "EXT_1") (pintype "passive"))
    )
    (net (code "35") (name "Net-(Q4-S)") (class "Default")
      (node (ref "Q4") (pin "2") (pinfunction "S_2") (pintype "passive"))
      (node (ref "R12") (pin "1") (pinfunction "1_1") (pintype "passive"))
      (node (ref "U8") (pin "8") (pinfunction "CS_8") (pintype "passive"))
    )
    (net (code "36") (name "Net-(U1-RSET)") (class "Default")
      (node (ref "R5") (pin "2") (pinfunction "2_2") (pintype "passive"))
      (node (ref "U1") (pin "3") (pinfunction "RSET_3") (pintype "passive"))
    )
    (net (code "37") (name "Net-(U1-VOUT)") (class "Default")
      (node (ref "C5") (pin "2") (pinfunction "2_2") (pintype "passive"))
      (node (ref "H1") (pin "2") (pinfunction "2_2") (pintype "passive"))
      (node (ref "L1") (pin "1") (pinfunction "1_1") (pintype "passive"))
      (node (ref "U1") (pin "1") (pinfunction "VOUT_1") (pintype "passive"))
    )
    (net (code "38") (name "Net-(U2-RSET)") (class "Default")
      (node (ref "R6") (pin "2") (pinfunction "2_2") (pintype "passive"))
      (node (ref "U2") (pin "3") (pinfunction "RSET_3") (pintype "passive"))
    )
    (net (code "39") (name "Net-(U2-VOUT)") (class "Default")
      (node (ref "C6") (pin "2") (pinfunction "2_2") (pintype "passive"))
      (node (ref "H2") (pin "2") (pinfunction "2_2") (pintype "passive"))
      (node (ref "L2") (pin "1") (pinfunction "1_1") (pintype "passive"))
      (node (ref "U2") (pin "1") (pinfunction "VOUT_1") (pintype "passive"))
    )
    (net (code "40") (name "Net-(U3-RSET)") (class "Default")
      (node (ref "R7") (pin "2") (pinfunction "2_2") (pintype "passive"))
      (node (ref "U3") (pin "3") (pinfunction "RSET_3") (pintype "passive"))
    )
    (net (code "41") (name "Net-(U3-VOUT)") (class "Default")
      (node (ref "C7") (pin "2") (pinfunction "2_2") (pintype "passive"))
      (node (ref "H3") (pin "2") (pinfunction "2_2") (pintype "passive"))
      (node (ref "L3") (pin "1") (pinfunction "1_1") (pintype "passive"))
      (node (ref "U3") (pin "1") (pinfunction "VOUT_1") (pintype "passive"))
    )
    (net (code "42") (name "Net-(U4-RSET)") (class "Default")
      (node (ref "R8") (pin "2") (pinfunction "2_2") (pintype "passive"))
      (node (ref "U4") (pin "3") (pinfunction "RSET_3") (pintype "passive"))
    )
    (net (code "43") (name "Net-(U4-VOUT)") (class "Default")
      (node (ref "C8") (pin "2") (pinfunction "2_2") (pintype "passive"))
      (node (ref "H4") (pin "2") (pinfunction "2_2") (pintype "passive"))
      (node (ref "L4") (pin "1") (pinfunction "1_1") (pintype "passive"))
      (node (ref "U4") (pin "1") (pinfunction "VOUT_1") (pintype "passive"))
    )
    (net (code "44") (name "Net-(U5-FB)") (class "Default")
      (node (ref "R13") (pin "1") (pinfunction "1_1") (pintype "passive"))
      (node (ref "R16") (pin "1") (pinfunction "1_1") (pintype "passive"))
      (node (ref "U5") (pin "3") (pinfunction "FB_3") (pintype "passive"))
    )
    (net (code "45") (name "Net-(U5-REF)") (class "Default")
      (node (ref "C9") (pin "2") (pinfunction "2_2") (pintype "passive"))
      (node (ref "U5") (pin "5") (pinfunction "REF_5") (pintype "passive"))
    )
    (net (code "46") (name "Net-(U6-FB)") (class "Default")
      (node (ref "R14") (pin "1") (pinfunction "1_1") (pintype "passive"))
      (node (ref "R17") (pin "1") (pinfunction "1_1") (pintype "passive"))
      (node (ref "U6") (pin "3") (pinfunction "FB_3") (pintype "passive"))
    )
    (net (code "47") (name "Net-(U6-REF)") (class "Default")
      (node (ref "C10") (pin "2") (pinfunction "2_2") (pintype "passive"))
      (node (ref "U6") (pin "5") (pinfunction "REF_5") (pintype "passive"))
    )
    (net (code "48") (name "Net-(U7-FB)") (class "Default")
      (node (ref "R15") (pin "1") (pinfunction "1_1") (pintype "passive"))
      (node (ref "R18") (pin "1") (pinfunction "1_1") (pintype "passive"))
      (node (ref "U7") (pin "3") (pinfunction "FB_3") (pintype "passive"))
    )
    (net (code "49") (name "Net-(U7-REF)") (class "Default")
      (node (ref "C11") (pin "2") (pinfunction "2_2") (pintype "passive"))
      (node (ref "U7") (pin "5") (pinfunction "REF_5") (pintype "passive"))
    )
    (net (code "50") (name "Net-(U8-FB)") (class "Default")
      (node (ref "R19") (pin "1") (pinfunction "1_1") (pintype "passive"))
      (node (ref "R20") (pin "1") (pinfunction "1_1") (pintype "passive"))
      (node (ref "U8") (pin "3") (pinfunction "FB_3") (pintype "passive"))
    )
    (net (code "51") (name "Net-(U8-REF)") (class "Default")
      (node (ref "C12") (pin "2") (pinfunction "2_2") (pintype "passive"))
      (node (ref "U8") (pin "5") (pinfunction "REF_5") (pintype "passive"))
    )
    (net (code "52") (name "Net-(U9-PA0)") (class "Default")
      (node (ref "R16") (pin "2") (pinfunction "2_2") (pintype "passive"))
      (node (ref "U9") (pin "5") (pinfunction "PA0_5") (pintype "passive"))
      (node (ref "U9") (pin "6") (pinfunction "PW0_6") (pintype "passive"))
    )
    (net (code "53") (name "Net-(U10-PA0)") (class "Default")
      (node (ref "R17") (pin "2") (pinfunction "2_2") (pintype "passive"))
      (node (ref "U10") (pin "5") (pinfunction "PA0_5") (pintype "passive"))
      (node (ref "U10") (pin "6") (pinfunction "PW0_6") (pintype "passive"))
    )
    (net (code "54") (name "Net-(U11-PA0)") (class "Default")
      (node (ref "R18") (pin "2") (pinfunction "2_2") (pintype "passive"))
      (node (ref "U11") (pin "5") (pinfunction "PA0_5") (pintype "passive"))
      (node (ref "U11") (pin "6") (pinfunction "PW0_6") (pintype "passive"))
    )
    (net (code "55") (name "Net-(U12-PA0)") (class "Default")
      (node (ref "R20") (pin "2") (pinfunction "2_2") (pintype "passive"))
      (node (ref "U12") (pin "5") (pinfunction "PA0_5") (pintype "passive"))
      (node (ref "U12") (pin "6") (pinfunction "PW0_6") (pintype "passive"))
    )
    (net (code "56") (name "Net-(U18A-IN1+)") (class "Default")
      (node (ref "R23") (pin "1") (pinfunction "1_1") (pintype "passive"))
      (node (ref "R24") (pin "2") (pinfunction "2_2") (pintype "passive"))
      (node (ref "U18") (pin "3") (pinfunction "IN1+_3") (pintype "passive"))
    )
    (net (code "57") (name "Net-(U18B-IN2+)") (class "Default")
      (node (ref "R25") (pin "1") (pinfunction "1_1") (pintype "passive"))
      (node (ref "R26") (pin "2") (pinfunction "2_2") (pintype "passive"))
      (node (ref "U18") (pin "5") (pinfunction "IN2+_5") (pintype "passive"))
    )
    (net (code "58") (name "Net-(U19A-IN1+)") (class "Default")
      (node (ref "R29") (pin "1") (pinfunction "1_1") (pintype "passive"))
      (node (ref "R30") (pin "2") (pinfunction "2_2") (pintype "passive"))
      (node (ref "U19") (pin "3") (pinfunction "IN1+_3") (pintype "passive"))
    )
    (net (code "59") (name "Net-(U19B-IN2+)") (class "Default")
      (node (ref "R27") (pin "1") (pinfunction "1_1") (pintype "passive"))
      (node (ref "R28") (pin "2") (pinfunction "2_2") (pintype "passive"))
      (node (ref "U19") (pin "5") (pinfunction "IN2+_5") (pintype "passive"))
    )
  )
)
